# placa_taca_2_0.net
KiCad netlist of a schematic drawn in EAGLE
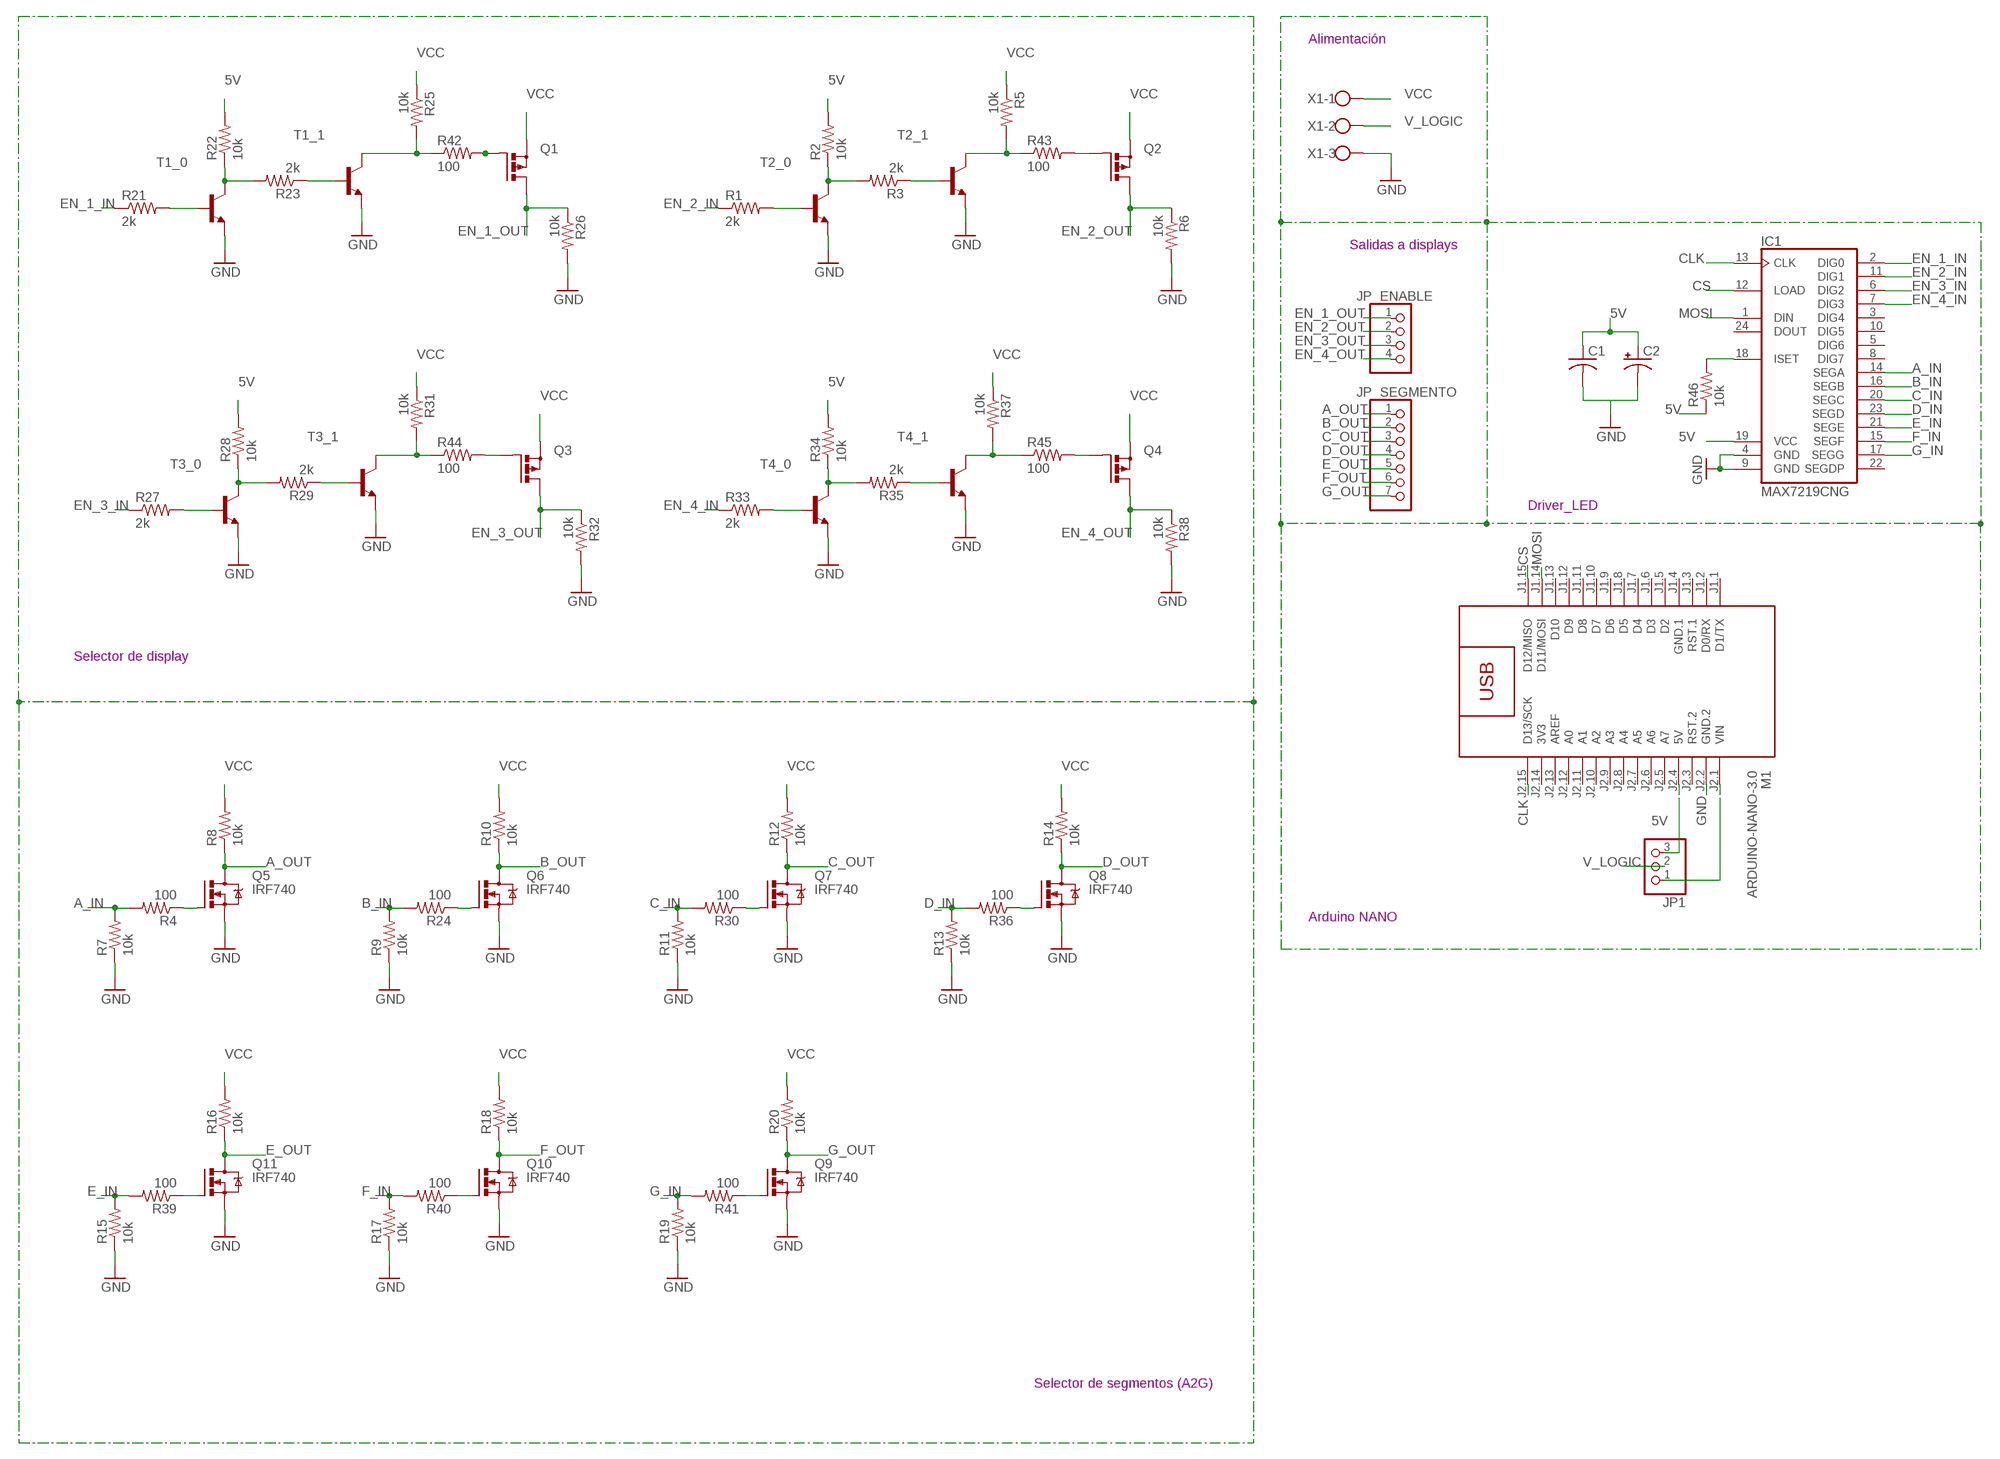
[diagram p0: schematic, sheet 1]

(export (version "E")
  (design (tool "Eeschema 10.0.6"))
  (components
    (comp (ref "C1")
      (value "C-US025-030X050")
      (footprint "eagle-import:C025-030X050")
      (libsource (lib "eagle-import") (part "C-US025-030X050"))
    )
    (comp (ref "C2")
      (value "CPOL-USE2.5-5")
      (footprint "eagle-import:E2,5-5")
      (libsource (lib "eagle-import") (part "CPOL-USE2.5-5"))
    )
    (comp (ref "IC1")
      (value "MAX7219CNG")
      (footprint "eagle-import:DIL24-3")
      (fields (field (name "MF") "MAXIM"))
      (libsource (lib "eagle-import") (part "MAX7219CNG"))
    )
    (comp (ref "JP1")
      (value "PINHD-1X3")
      (footprint "eagle-import:1X03")
      (libsource (lib "eagle-import") (part "PINHD-1X3"))
    )
    (comp (ref "JP_ENABLE")
      (value "PINHD-1X4")
      (footprint "eagle-import:1X04")
      (libsource (lib "eagle-import") (part "PINHD-1X4"))
    )
    (comp (ref "JP_SEGMENTO")
      (value "PINHD-1X7")
      (footprint "eagle-import:1X07")
      (libsource (lib "eagle-import") (part "PINHD-1X7"))
    )
    (comp (ref "M1")
      (value "ARDUINO-NANO-3.0")
      (footprint "eagle-import:ARDUINO-NANO-3.0")
      (libsource (lib "eagle-import") (part "ARDUINO-NANO-3.0"))
    )
    (comp (ref "Q1")
      (value "PMOSFET_PTO220BV")
      (footprint "eagle-import:TO220BV")
      (libsource (lib "eagle-import") (part "PMOSFET_PTO220BV"))
    )
    (comp (ref "Q2")
      (value "PMOSFET_PTO220BV")
      (footprint "eagle-import:TO220BV")
      (libsource (lib "eagle-import") (part "PMOSFET_PTO220BV"))
    )
    (comp (ref "Q3")
      (value "PMOSFET_PTO220BV")
      (footprint "eagle-import:TO220BV")
      (libsource (lib "eagle-import") (part "PMOSFET_PTO220BV"))
    )
    (comp (ref "Q4")
      (value "PMOSFET_PTO220BV")
      (footprint "eagle-import:TO220BV")
      (libsource (lib "eagle-import") (part "PMOSFET_PTO220BV"))
    )
    (comp (ref "Q5")
      (value "IRF740")
      (footprint "eagle-import:TO220BV")
      (libsource (lib "eagle-import") (part "IRF740"))
    )
    (comp (ref "Q6")
      (value "IRF740")
      (footprint "eagle-import:TO220BV")
      (libsource (lib "eagle-import") (part "IRF740"))
    )
    (comp (ref "Q7")
      (value "IRF740")
      (footprint "eagle-import:TO220BV")
      (libsource (lib "eagle-import") (part "IRF740"))
    )
    (comp (ref "Q8")
      (value "IRF740")
      (footprint "eagle-import:TO220BV")
      (libsource (lib "eagle-import") (part "IRF740"))
    )
    (comp (ref "Q9")
      (value "IRF740")
      (footprint "eagle-import:TO220BV")
      (libsource (lib "eagle-import") (part "IRF740"))
    )
    (comp (ref "Q10")
      (value "IRF740")
      (footprint "eagle-import:TO220BV")
      (libsource (lib "eagle-import") (part "IRF740"))
    )
    (comp (ref "Q11")
      (value "IRF740")
      (footprint "eagle-import:TO220BV")
      (libsource (lib "eagle-import") (part "IRF740"))
    )
    (comp (ref "R1")
      (value "2k")
      (footprint "eagle-import:0207_10")
      (libsource (lib "eagle-import") (part "R-US_0207/10"))
    )
    (comp (ref "R2")
      (value "10k")
      (footprint "eagle-import:0207_10")
      (libsource (lib "eagle-import") (part "R-US_0207/10"))
    )
    (comp (ref "R3")
      (value "2k")
      (footprint "eagle-import:0207_10")
      (libsource (lib "eagle-import") (part "R-US_0207/10"))
    )
    (comp (ref "R4")
      (value "100")
      (footprint "eagle-import:0207_10")
      (libsource (lib "eagle-import") (part "R-US_0207/10"))
    )
    (comp (ref "R5")
      (value "10k")
      (footprint "eagle-import:0207_10")
      (libsource (lib "eagle-import") (part "R-US_0207/10"))
    )
    (comp (ref "R6")
      (value "10k")
      (footprint "eagle-import:0207_10")
      (libsource (lib "eagle-import") (part "R-US_0207/10"))
    )
    (comp (ref "R7")
      (value "10k")
      (footprint "eagle-import:0207_10")
      (libsource (lib "eagle-import") (part "R-US_0207/10"))
    )
    (comp (ref "R8")
      (value "10k")
      (footprint "eagle-import:0207_10")
      (libsource (lib "eagle-import") (part "R-US_0207/10"))
    )
    (comp (ref "R9")
      (value "10k")
      (footprint "eagle-import:0207_10")
      (libsource (lib "eagle-import") (part "R-US_0207/10"))
    )
    (comp (ref "R10")
      (value "10k")
      (footprint "eagle-import:0207_10")
      (libsource (lib "eagle-import") (part "R-US_0207/10"))
    )
    (comp (ref "R11")
      (value "10k")
      (footprint "eagle-import:0207_10")
      (libsource (lib "eagle-import") (part "R-US_0207/10"))
    )
    (comp (ref "R12")
      (value "10k")
      (footprint "eagle-import:0207_10")
      (libsource (lib "eagle-import") (part "R-US_0207/10"))
    )
    (comp (ref "R13")
      (value "10k")
      (footprint "eagle-import:0207_10")
      (libsource (lib "eagle-import") (part "R-US_0207/10"))
    )
    (comp (ref "R14")
      (value "10k")
      (footprint "eagle-import:0207_10")
      (libsource (lib "eagle-import") (part "R-US_0207/10"))
    )
    (comp (ref "R15")
      (value "10k")
      (footprint "eagle-import:0207_10")
      (libsource (lib "eagle-import") (part "R-US_0207/10"))
    )
    (comp (ref "R16")
      (value "10k")
      (footprint "eagle-import:0207_10")
      (libsource (lib "eagle-import") (part "R-US_0207/10"))
    )
    (comp (ref "R17")
      (value "10k")
      (footprint "eagle-import:0207_10")
      (libsource (lib "eagle-import") (part "R-US_0207/10"))
    )
    (comp (ref "R18")
      (value "10k")
      (footprint "eagle-import:0207_10")
      (libsource (lib "eagle-import") (part "R-US_0207/10"))
    )
    (comp (ref "R19")
      (value "10k")
      (footprint "eagle-import:0207_10")
      (libsource (lib "eagle-import") (part "R-US_0207/10"))
    )
    (comp (ref "R20")
      (value "10k")
      (footprint "eagle-import:0207_10")
      (libsource (lib "eagle-import") (part "R-US_0207/10"))
    )
    (comp (ref "R21")
      (value "2k")
      (footprint "eagle-import:0207_10")
      (libsource (lib "eagle-import") (part "R-US_0207/10"))
    )
    (comp (ref "R22")
      (value "10k")
      (footprint "eagle-import:0207_10")
      (libsource (lib "eagle-import") (part "R-US_0207/10"))
    )
    (comp (ref "R23")
      (value "2k")
      (footprint "eagle-import:0207_10")
      (libsource (lib "eagle-import") (part "R-US_0207/10"))
    )
    (comp (ref "R24")
      (value "100")
      (footprint "eagle-import:0207_10")
      (libsource (lib "eagle-import") (part "R-US_0207/10"))
    )
    (comp (ref "R25")
      (value "10k")
      (footprint "eagle-import:0207_10")
      (libsource (lib "eagle-import") (part "R-US_0207/10"))
    )
    (comp (ref "R26")
      (value "10k")
      (footprint "eagle-import:0207_10")
      (libsource (lib "eagle-import") (part "R-US_0207/10"))
    )
    (comp (ref "R27")
      (value "2k")
      (footprint "eagle-import:0207_10")
      (libsource (lib "eagle-import") (part "R-US_0207/10"))
    )
    (comp (ref "R28")
      (value "10k")
      (footprint "eagle-import:0207_10")
      (libsource (lib "eagle-import") (part "R-US_0207/10"))
    )
    (comp (ref "R29")
      (value "2k")
      (footprint "eagle-import:0207_10")
      (libsource (lib "eagle-import") (part "R-US_0207/10"))
    )
    (comp (ref "R30")
      (value "100")
      (footprint "eagle-import:0207_10")
      (libsource (lib "eagle-import") (part "R-US_0207/10"))
    )
    (comp (ref "R31")
      (value "10k")
      (footprint "eagle-import:0207_10")
      (libsource (lib "eagle-import") (part "R-US_0207/10"))
    )
    (comp (ref "R32")
      (value "10k")
      (footprint "eagle-import:0207_10")
      (libsource (lib "eagle-import") (part "R-US_0207/10"))
    )
    (comp (ref "R33")
      (value "2k")
      (footprint "eagle-import:0207_10")
      (libsource (lib "eagle-import") (part "R-US_0207/10"))
    )
    (comp (ref "R34")
      (value "10k")
      (footprint "eagle-import:0207_10")
      (libsource (lib "eagle-import") (part "R-US_0207/10"))
    )
    (comp (ref "R35")
      (value "2k")
      (footprint "eagle-import:0207_10")
      (libsource (lib "eagle-import") (part "R-US_0207/10"))
    )
    (comp (ref "R36")
      (value "100")
      (footprint "eagle-import:0207_10")
      (libsource (lib "eagle-import") (part "R-US_0207/10"))
    )
    (comp (ref "R37")
      (value "10k")
      (footprint "eagle-import:0207_10")
      (libsource (lib "eagle-import") (part "R-US_0207/10"))
    )
    (comp (ref "R38")
      (value "10k")
      (footprint "eagle-import:0207_10")
      (libsource (lib "eagle-import") (part "R-US_0207/10"))
    )
    (comp (ref "R39")
      (value "100")
      (footprint "eagle-import:0207_10")
      (libsource (lib "eagle-import") (part "R-US_0207/10"))
    )
    (comp (ref "R40")
      (value "100")
      (footprint "eagle-import:0207_10")
      (libsource (lib "eagle-import") (part "R-US_0207/10"))
    )
    (comp (ref "R41")
      (value "100")
      (footprint "eagle-import:0207_10")
      (libsource (lib "eagle-import") (part "R-US_0207/10"))
    )
    (comp (ref "R42")
      (value "100")
      (footprint "eagle-import:0207_10")
      (libsource (lib "eagle-import") (part "R-US_0207/10"))
    )
    (comp (ref "R43")
      (value "100")
      (footprint "eagle-import:0207_10")
      (libsource (lib "eagle-import") (part "R-US_0207/10"))
    )
    (comp (ref "R44")
      (value "100")
      (footprint "eagle-import:0207_10")
      (libsource (lib "eagle-import") (part "R-US_0207/10"))
    )
    (comp (ref "R45")
      (value "100")
      (footprint "eagle-import:0207_10")
      (libsource (lib "eagle-import") (part "R-US_0207/10"))
    )
    (comp (ref "R46")
      (value "10k")
      (footprint "eagle-import:0207_10")
      (libsource (lib "eagle-import") (part "R-US_0207/10"))
    )
    (comp (ref "T1_0")
      (value "2N2222-NPN-TO92-EBC")
      (footprint "eagle-import:TO92-EBC")
      (libsource (lib "eagle-import") (part "-NPN-TO92-EBC2N2222"))
    )
    (comp (ref "T1_1")
      (value "2N2222-NPN-TO92-EBC")
      (footprint "eagle-import:TO92-EBC")
      (libsource (lib "eagle-import") (part "-NPN-TO92-EBC2N2222"))
    )
    (comp (ref "T2_0")
      (value "2N2222-NPN-TO92-EBC")
      (footprint "eagle-import:TO92-EBC")
      (libsource (lib "eagle-import") (part "-NPN-TO92-EBC2N2222"))
    )
    (comp (ref "T2_1")
      (value "2N2222-NPN-TO92-EBC")
      (footprint "eagle-import:TO92-EBC")
      (libsource (lib "eagle-import") (part "-NPN-TO92-EBC2N2222"))
    )
    (comp (ref "T3_0")
      (value "2N2222-NPN-TO92-EBC")
      (footprint "eagle-import:TO92-EBC")
      (libsource (lib "eagle-import") (part "-NPN-TO92-EBC2N2222"))
    )
    (comp (ref "T3_1")
      (value "2N2222-NPN-TO92-EBC")
      (footprint "eagle-import:TO92-EBC")
      (libsource (lib "eagle-import") (part "-NPN-TO92-EBC2N2222"))
    )
    (comp (ref "T4_0")
      (value "2N2222-NPN-TO92-EBC")
      (footprint "eagle-import:TO92-EBC")
      (libsource (lib "eagle-import") (part "-NPN-TO92-EBC2N2222"))
    )
    (comp (ref "T4_1")
      (value "2N2222-NPN-TO92-EBC")
      (footprint "eagle-import:TO92-EBC")
      (libsource (lib "eagle-import") (part "-NPN-TO92-EBC2N2222"))
    )
    (comp (ref "X1")
      (value "W237-103")
      (footprint "eagle-import:W237-103")
      (fields (field (name "MPN") "237-103"))
      (libsource (lib "eagle-import") (part "W237-103"))
    )
  )
  (nets
    (net (code "1") (name "/3V3") (class "Default")
      (node (ref "M1") (pin "J2.14") (pinfunction "3V3_J2.14") (pintype "power_in"))
    )
    (net (code "2") (name "/5V") (class "Default")
      (node (ref "C1") (pin "1") (pinfunction "1_1") (pintype "passive"))
      (node (ref "C2") (pin "+") (pinfunction "+_+") (pintype "passive"))
      (node (ref "IC1") (pin "19") (pinfunction "VCC_19") (pintype "power_in"))
      (node (ref "JP1") (pin "3") (pinfunction "3_3") (pintype "passive"))
      (node (ref "M1") (pin "J2.4") (pinfunction "5V_J2.4") (pintype "power_in"))
      (node (ref "R2") (pin "2") (pinfunction "2_2") (pintype "passive"))
      (node (ref "R22") (pin "2") (pinfunction "2_2") (pintype "passive"))
      (node (ref "R28") (pin "2") (pinfunction "2_2") (pintype "passive"))
      (node (ref "R34") (pin "2") (pinfunction "2_2") (pintype "passive"))
      (node (ref "R46") (pin "1") (pinfunction "1_1") (pintype "passive"))
    )
    (net (code "3") (name "/A_IN") (class "Default")
      (node (ref "IC1") (pin "14") (pinfunction "SEGA_14") (pintype "output"))
      (node (ref "R4") (pin "2") (pinfunction "2_2") (pintype "passive"))
      (node (ref "R7") (pin "2") (pinfunction "2_2") (pintype "passive"))
    )
    (net (code "4") (name "/A_OUT") (class "Default")
      (node (ref "JP_SEGMENTO") (pin "1") (pinfunction "1_1") (pintype "passive"))
      (node (ref "Q5") (pin "D") (pinfunction "D_D") (pintype "passive"))
      (node (ref "R8") (pin "1") (pinfunction "1_1") (pintype "passive"))
    )
    (net (code "5") (name "/B_IN") (class "Default")
      (node (ref "IC1") (pin "16") (pinfunction "SEGB_16") (pintype "output"))
      (node (ref "R24") (pin "2") (pinfunction "2_2") (pintype "passive"))
      (node (ref "R9") (pin "2") (pinfunction "2_2") (pintype "passive"))
    )
    (net (code "6") (name "/B_OUT") (class "Default")
      (node (ref "JP_SEGMENTO") (pin "2") (pinfunction "2_2") (pintype "passive"))
      (node (ref "Q6") (pin "D") (pinfunction "D_D") (pintype "passive"))
      (node (ref "R10") (pin "1") (pinfunction "1_1") (pintype "passive"))
    )
    (net (code "7") (name "/CLK") (class "Default")
      (node (ref "IC1") (pin "13") (pinfunction "CLK_13") (pintype "input"))
      (node (ref "M1") (pin "J2.15") (pinfunction "D13/SCK_J2.15") (pintype "bidirectional"))
    )
    (net (code "8") (name "/CS") (class "Default")
      (node (ref "IC1") (pin "12") (pinfunction "LOAD_12") (pintype "input"))
      (node (ref "M1") (pin "J1.15") (pinfunction "D12/MISO_J1.15") (pintype "bidirectional"))
    )
    (net (code "9") (name "/C_IN") (class "Default")
      (node (ref "IC1") (pin "20") (pinfunction "SEGC_20") (pintype "output"))
      (node (ref "R11") (pin "2") (pinfunction "2_2") (pintype "passive"))
      (node (ref "R30") (pin "2") (pinfunction "2_2") (pintype "passive"))
    )
    (net (code "10") (name "/C_OUT") (class "Default")
      (node (ref "JP_SEGMENTO") (pin "3") (pinfunction "3_3") (pintype "passive"))
      (node (ref "Q7") (pin "D") (pinfunction "D_D") (pintype "passive"))
      (node (ref "R12") (pin "1") (pinfunction "1_1") (pintype "passive"))
    )
    (net (code "11") (name "/D_IN") (class "Default")
      (node (ref "IC1") (pin "23") (pinfunction "SEGD_23") (pintype "output"))
      (node (ref "R13") (pin "2") (pinfunction "2_2") (pintype "passive"))
      (node (ref "R36") (pin "2") (pinfunction "2_2") (pintype "passive"))
    )
    (net (code "12") (name "/D_OUT") (class "Default")
      (node (ref "JP_SEGMENTO") (pin "4") (pinfunction "4_4") (pintype "passive"))
      (node (ref "Q8") (pin "D") (pinfunction "D_D") (pintype "passive"))
      (node (ref "R14") (pin "1") (pinfunction "1_1") (pintype "passive"))
    )
    (net (code "13") (name "/EN_1_IN") (class "Default")
      (node (ref "IC1") (pin "2") (pinfunction "DIG0_2") (pintype "output"))
      (node (ref "R21") (pin "1") (pinfunction "1_1") (pintype "passive"))
    )
    (net (code "14") (name "/EN_1_OUT") (class "Default")
      (node (ref "JP_ENABLE") (pin "1") (pinfunction "1_1") (pintype "passive"))
      (node (ref "Q1") (pin "D") (pinfunction "D_D") (pintype "passive"))
      (node (ref "R26") (pin "1") (pinfunction "1_1") (pintype "passive"))
    )
    (net (code "15") (name "/EN_2_IN") (class "Default")
      (node (ref "IC1") (pin "11") (pinfunction "DIG1_11") (pintype "output"))
      (node (ref "R1") (pin "1") (pinfunction "1_1") (pintype "passive"))
    )
    (net (code "16") (name "/EN_2_OUT") (class "Default")
      (node (ref "JP_ENABLE") (pin "2") (pinfunction "2_2") (pintype "passive"))
      (node (ref "Q2") (pin "D") (pinfunction "D_D") (pintype "passive"))
      (node (ref "R6") (pin "1") (pinfunction "1_1") (pintype "passive"))
    )
    (net (code "17") (name "/EN_3_IN") (class "Default")
      (node (ref "IC1") (pin "6") (pinfunction "DIG2_6") (pintype "output"))
      (node (ref "R27") (pin "1") (pinfunction "1_1") (pintype "passive"))
    )
    (net (code "18") (name "/EN_3_OUT") (class "Default")
      (node (ref "JP_ENABLE") (pin "3") (pinfunction "3_3") (pintype "passive"))
      (node (ref "Q3") (pin "D") (pinfunction "D_D") (pintype "passive"))
      (node (ref "R32") (pin "1") (pinfunction "1_1") (pintype "passive"))
    )
    (net (code "19") (name "/EN_4_IN") (class "Default")
      (node (ref "IC1") (pin "7") (pinfunction "DIG3_7") (pintype "output"))
      (node (ref "R33") (pin "1") (pinfunction "1_1") (pintype "passive"))
    )
    (net (code "20") (name "/EN_4_OUT") (class "Default")
      (node (ref "JP_ENABLE") (pin "4") (pinfunction "4_4") (pintype "passive"))
      (node (ref "Q4") (pin "D") (pinfunction "D_D") (pintype "passive"))
      (node (ref "R38") (pin "1") (pinfunction "1_1") (pintype "passive"))
    )
    (net (code "21") (name "/E_IN") (class "Default")
      (node (ref "IC1") (pin "21") (pinfunction "SEGE_21") (pintype "output"))
      (node (ref "R15") (pin "2") (pinfunction "2_2") (pintype "passive"))
      (node (ref "R39") (pin "2") (pinfunction "2_2") (pintype "passive"))
    )
    (net (code "22") (name "/E_OUT") (class "Default")
      (node (ref "JP_SEGMENTO") (pin "5") (pinfunction "5_5") (pintype "passive"))
      (node (ref "Q11") (pin "D") (pinfunction "D_D") (pintype "passive"))
      (node (ref "R16") (pin "1") (pinfunction "1_1") (pintype "passive"))
    )
    (net (code "23") (name "/F_IN") (class "Default")
      (node (ref "IC1") (pin "15") (pinfunction "SEGF_15") (pintype "output"))
      (node (ref "R17") (pin "2") (pinfunction "2_2") (pintype "passive"))
      (node (ref "R40") (pin "2") (pinfunction "2_2") (pintype "passive"))
    )
    (net (code "24") (name "/F_OUT") (class "Default")
      (node (ref "JP_SEGMENTO") (pin "6") (pinfunction "6_6") (pintype "passive"))
      (node (ref "Q10") (pin "D") (pinfunction "D_D") (pintype "passive"))
      (node (ref "R18") (pin "1") (pinfunction "1_1") (pintype "passive"))
    )
    (net (code "25") (name "/GND.1") (class "Default")
      (node (ref "M1") (pin "J1.4") (pinfunction "GND.1_J1.4") (pintype "power_in"))
    )
    (net (code "26") (name "/G_IN") (class "Default")
      (node (ref "IC1") (pin "17") (pinfunction "SEGG_17") (pintype "output"))
      (node (ref "R19") (pin "2") (pinfunction "2_2") (pintype "passive"))
      (node (ref "R41") (pin "2") (pinfunction "2_2") (pintype "passive"))
    )
    (net (code "27") (name "/G_OUT") (class "Default")
      (node (ref "JP_SEGMENTO") (pin "7") (pinfunction "7_7") (pintype "passive"))
      (node (ref "Q9") (pin "D") (pinfunction "D_D") (pintype "passive"))
      (node (ref "R20") (pin "1") (pinfunction "1_1") (pintype "passive"))
    )
    (net (code "28") (name "/MOSI") (class "Default")
      (node (ref "IC1") (pin "1") (pinfunction "DIN_1") (pintype "input"))
      (node (ref "M1") (pin "J1.14") (pinfunction "D11/MOSI_J1.14") (pintype "bidirectional"))
    )
    (net (code "29") (name "/VCC") (class "Default")
      (node (ref "Q1") (pin "S") (pinfunction "S_S") (pintype "passive"))
      (node (ref "Q2") (pin "S") (pinfunction "S_S") (pintype "passive"))
      (node (ref "Q3") (pin "S") (pinfunction "S_S") (pintype "passive"))
      (node (ref "Q4") (pin "S") (pinfunction "S_S") (pintype "passive"))
      (node (ref "R10") (pin "2") (pinfunction "2_2") (pintype "passive"))
      (node (ref "R12") (pin "2") (pinfunction "2_2") (pintype "passive"))
      (node (ref "R14") (pin "2") (pinfunction "2_2") (pintype "passive"))
      (node (ref "R16") (pin "2") (pinfunction "2_2") (pintype "passive"))
      (node (ref "R18") (pin "2") (pinfunction "2_2") (pintype "passive"))
      (node (ref "R20") (pin "2") (pinfunction "2_2") (pintype "passive"))
      (node (ref "R25") (pin "1") (pinfunction "1_1") (pintype "passive"))
      (node (ref "R31") (pin "1") (pinfunction "1_1") (pintype "passive"))
      (node (ref "R37") (pin "1") (pinfunction "1_1") (pintype "passive"))
      (node (ref "R5") (pin "1") (pinfunction "1_1") (pintype "passive"))
      (node (ref "R8") (pin "2") (pinfunction "2_2") (pintype "passive"))
      (node (ref "X1") (pin "1") (pinfunction "KL_1") (pintype "passive"))
    )
    (net (code "30") (name "/V_LOGIC") (class "Default")
      (node (ref "JP1") (pin "2") (pinfunction "2_2") (pintype "passive"))
      (node (ref "X1") (pin "2") (pinfunction "KL_2") (pintype "passive"))
    )
    (net (code "31") (name "GND") (class "Default")
      (node (ref "IC1") (pin "4") (pinfunction "GND_4") (pintype "power_in"))
      (node (ref "IC1") (pin "9") (pinfunction "GND_9") (pintype "power_in"))
      (node (ref "M1") (pin "J2.2") (pinfunction "GND.2_J2.2") (pintype "power_in"))
      (node (ref "Q10") (pin "S") (pinfunction "S_S") (pintype "passive"))
      (node (ref "Q11") (pin "S") (pinfunction "S_S") (pintype "passive"))
      (node (ref "Q5") (pin "S") (pinfunction "S_S") (pintype "passive"))
      (node (ref "Q6") (pin "S") (pinfunction "S_S") (pintype "passive"))
      (node (ref "Q7") (pin "S") (pinfunction "S_S") (pintype "passive"))
      (node (ref "Q8") (pin "S") (pinfunction "S_S") (pintype "passive"))
      (node (ref "Q9") (pin "S") (pinfunction "S_S") (pintype "passive"))
      (node (ref "R11") (pin "1") (pinfunction "1_1") (pintype "passive"))
      (node (ref "R13") (pin "1") (pinfunction "1_1") (pintype "passive"))
      (node (ref "R15") (pin "1") (pinfunction "1_1") (pintype "passive"))
      (node (ref "R17") (pin "1") (pinfunction "1_1") (pintype "passive"))
      (node (ref "R19") (pin "1") (pinfunction "1_1") (pintype "passive"))
      (node (ref "R26") (pin "2") (pinfunction "2_2") (pintype "passive"))
      (node (ref "R32") (pin "2") (pinfunction "2_2") (pintype "passive"))
      (node (ref "R38") (pin "2") (pinfunction "2_2") (pintype "passive"))
      (node (ref "R6") (pin "2") (pinfunction "2_2") (pintype "passive"))
      (node (ref "R7") (pin "1") (pinfunction "1_1") (pintype "passive"))
      (node (ref "R9") (pin "1") (pinfunction "1_1") (pintype "passive"))
      (node (ref "T1_0") (pin "E") (pinfunction "E_E") (pintype "passive"))
      (node (ref "T1_1") (pin "E") (pinfunction "E_E") (pintype "passive"))
      (node (ref "T2_0") (pin "E") (pinfunction "E_E") (pintype "passive"))
      (node (ref "T2_1") (pin "E") (pinfunction "E_E") (pintype "passive"))
      (node (ref "T3_0") (pin "E") (pinfunction "E_E") (pintype "passive"))
      (node (ref "T3_1") (pin "E") (pinfunction "E_E") (pintype "passive"))
      (node (ref "T4_0") (pin "E") (pinfunction "E_E") (pintype "passive"))
      (node (ref "T4_1") (pin "E") (pinfunction "E_E") (pintype "passive"))
      (node (ref "X1") (pin "3") (pinfunction "KL_3") (pintype "passive"))
    )
    (net (code "32") (name "Net-(C1-Pad2)") (class "Default")
      (node (ref "C1") (pin "2") (pinfunction "2_2") (pintype "passive"))
      (node (ref "C2") (pin "-") (pinfunction "-_-") (pintype "passive"))
    )
    (net (code "33") (name "Net-(IC1-ISET)") (class "Default")
      (node (ref "IC1") (pin "18") (pinfunction "ISET_18") (pintype "input"))
      (node (ref "R46") (pin "2") (pinfunction "2_2") (pintype "passive"))
    )
    (net (code "34") (name "Net-(M1-VIN)") (class "Default")
      (node (ref "JP1") (pin "1") (pinfunction "1_1") (pintype "passive"))
      (node (ref "M1") (pin "J2.1") (pinfunction "VIN_J2.1") (pintype "power_in"))
    )
    (net (code "35") (name "Net-(Q1-PadG)") (class "Default")
      (node (ref "Q1") (pin "G") (pinfunction "G_G") (pintype "passive"))
      (node (ref "R42") (pin "2") (pinfunction "2_2") (pintype "passive"))
    )
    (net (code "36") (name "Net-(Q2-PadG)") (class "Default")
      (node (ref "Q2") (pin "G") (pinfunction "G_G") (pintype "passive"))
      (node (ref "R43") (pin "2") (pinfunction "2_2") (pintype "passive"))
    )
    (net (code "37") (name "Net-(Q3-PadG)") (class "Default")
      (node (ref "Q3") (pin "G") (pinfunction "G_G") (pintype "passive"))
      (node (ref "R44") (pin "2") (pinfunction "2_2") (pintype "passive"))
    )
    (net (code "38") (name "Net-(Q4-PadG)") (class "Default")
      (node (ref "Q4") (pin "G") (pinfunction "G_G") (pintype "passive"))
      (node (ref "R45") (pin "2") (pinfunction "2_2") (pintype "passive"))
    )
    (net (code "39") (name "Net-(Q5-PadG)") (class "Default")
      (node (ref "Q5") (pin "G") (pinfunction "G_G") (pintype "passive"))
      (node (ref "R4") (pin "1") (pinfunction "1_1") (pintype "passive"))
    )
    (net (code "40") (name "Net-(Q6-PadG)") (class "Default")
      (node (ref "Q6") (pin "G") (pinfunction "G_G") (pintype "passive"))
      (node (ref "R24") (pin "1") (pinfunction "1_1") (pintype "passive"))
    )
    (net (code "41") (name "Net-(Q7-PadG)") (class "Default")
      (node (ref "Q7") (pin "G") (pinfunction "G_G") (pintype "passive"))
      (node (ref "R30") (pin "1") (pinfunction "1_1") (pintype "passive"))
    )
    (net (code "42") (name "Net-(Q8-PadG)") (class "Default")
      (node (ref "Q8") (pin "G") (pinfunction "G_G") (pintype "passive"))
      (node (ref "R36") (pin "1") (pinfunction "1_1") (pintype "passive"))
    )
    (net (code "43") (name "Net-(Q9-PadG)") (class "Default")
      (node (ref "Q9") (pin "G") (pinfunction "G_G") (pintype "passive"))
      (node (ref "R41") (pin "1") (pinfunction "1_1") (pintype "passive"))
    )
    (net (code "44") (name "Net-(Q10-PadG)") (class "Default")
      (node (ref "Q10") (pin "G") (pinfunction "G_G") (pintype "passive"))
      (node (ref "R40") (pin "1") (pinfunction "1_1") (pintype "passive"))
    )
    (net (code "45") (name "Net-(Q11-PadG)") (class "Default")
      (node (ref "Q11") (pin "G") (pinfunction "G_G") (pintype "passive"))
      (node (ref "R39") (pin "1") (pinfunction "1_1") (pintype "passive"))
    )
    (net (code "46") (name "Net-(R1-Pad2)") (class "Default")
      (node (ref "R1") (pin "2") (pinfunction "2_2") (pintype "passive"))
      (node (ref "T2_0") (pin "B") (pinfunction "B_B") (pintype "passive"))
    )
    (net (code "47") (name "Net-(R2-Pad1)") (class "Default")
      (node (ref "R2") (pin "1") (pinfunction "1_1") (pintype "passive"))
      (node (ref "R3") (pin "2") (pinfunction "2_2") (pintype "passive"))
      (node (ref "T2_0") (pin "C") (pinfunction "C_C") (pintype "passive"))
    )
    (net (code "48") (name "Net-(R3-Pad1)") (class "Default")
      (node (ref "R3") (pin "1") (pinfunction "1_1") (pintype "passive"))
      (node (ref "T2_1") (pin "B") (pinfunction "B_B") (pintype "passive"))
    )
    (net (code "49") (name "Net-(R21-Pad2)") (class "Default")
      (node (ref "R21") (pin "2") (pinfunction "2_2") (pintype "passive"))
      (node (ref "T1_0") (pin "B") (pinfunction "B_B") (pintype "passive"))
    )
    (net (code "50") (name "Net-(R22-Pad1)") (class "Default")
      (node (ref "R22") (pin "1") (pinfunction "1_1") (pintype "passive"))
      (node (ref "R23") (pin "2") (pinfunction "2_2") (pintype "passive"))
      (node (ref "T1_0") (pin "C") (pinfunction "C_C") (pintype "passive"))
    )
    (net (code "51") (name "Net-(R23-Pad1)") (class "Default")
      (node (ref "R23") (pin "1") (pinfunction "1_1") (pintype "passive"))
      (node (ref "T1_1") (pin "B") (pinfunction "B_B") (pintype "passive"))
    )
    (net (code "52") (name "Net-(R25-Pad2)") (class "Default")
      (node (ref "R25") (pin "2") (pinfunction "2_2") (pintype "passive"))
      (node (ref "R42") (pin "1") (pinfunction "1_1") (pintype "passive"))
      (node (ref "T1_1") (pin "C") (pinfunction "C_C") (pintype "passive"))
    )
    (net (code "53") (name "Net-(R27-Pad2)") (class "Default")
      (node (ref "R27") (pin "2") (pinfunction "2_2") (pintype "passive"))
      (node (ref "T3_0") (pin "B") (pinfunction "B_B") (pintype "passive"))
    )
    (net (code "54") (name "Net-(R28-Pad1)") (class "Default")
      (node (ref "R28") (pin "1") (pinfunction "1_1") (pintype "passive"))
      (node (ref "R29") (pin "2") (pinfunction "2_2") (pintype "passive"))
      (node (ref "T3_0") (pin "C") (pinfunction "C_C") (pintype "passive"))
    )
    (net (code "55") (name "Net-(R29-Pad1)") (class "Default")
      (node (ref "R29") (pin "1") (pinfunction "1_1") (pintype "passive"))
      (node (ref "T3_1") (pin "B") (pinfunction "B_B") (pintype "passive"))
    )
    (net (code "56") (name "Net-(R31-Pad2)") (class "Default")
      (node (ref "R31") (pin "2") (pinfunction "2_2") (pintype "passive"))
      (node (ref "R44") (pin "1") (pinfunction "1_1") (pintype "passive"))
      (node (ref "T3_1") (pin "C") (pinfunction "C_C") (pintype "passive"))
    )
    (net (code "57") (name "Net-(R33-Pad2)") (class "Default")
      (node (ref "R33") (pin "2") (pinfunction "2_2") (pintype "passive"))
      (node (ref "T4_0") (pin "B") (pinfunction "B_B") (pintype "passive"))
    )
    (net (code "58") (name "Net-(R34-Pad1)") (class "Default")
      (node (ref "R34") (pin "1") (pinfunction "1_1") (pintype "passive"))
      (node (ref "R35") (pin "2") (pinfunction "2_2") (pintype "passive"))
      (node (ref "T4_0") (pin "C") (pinfunction "C_C") (pintype "passive"))
    )
    (net (code "59") (name "Net-(R35-Pad1)") (class "Default")
      (node (ref "R35") (pin "1") (pinfunction "1_1") (pintype "passive"))
      (node (ref "T4_1") (pin "B") (pinfunction "B_B") (pintype "passive"))
    )
    (net (code "60") (name "Net-(R37-Pad2)") (class "Default")
      (node (ref "R37") (pin "2") (pinfunction "2_2") (pintype "passive"))
      (node (ref "R45") (pin "1") (pinfunction "1_1") (pintype "passive"))
      (node (ref "T4_1") (pin "C") (pinfunction "C_C") (pintype "passive"))
    )
    (net (code "61") (name "Net-(R43-Pad1)") (class "Default")
      (node (ref "R43") (pin "1") (pinfunction "1_1") (pintype "passive"))
      (node (ref "R5") (pin "2") (pinfunction "2_2") (pintype "passive"))
      (node (ref "T2_1") (pin "C") (pinfunction "C_C") (pintype "passive"))
    )
    (net (code "62") (name "unconnected-(IC1-DIG4-Pad3)") (class "Default")
      (node (ref "IC1") (pin "3") (pinfunction "DIG4_3") (pintype "output"))
    )
    (net (code "63") (name "unconnected-(IC1-DIG5-Pad10)") (class "Default")
      (node (ref "IC1") (pin "10") (pinfunction "DIG5_10") (pintype "output"))
    )
    (net (code "64") (name "unconnected-(IC1-DIG6-Pad5)") (class "Default")
      (node (ref "IC1") (pin "5") (pinfunction "DIG6_5") (pintype "output"))
    )
    (net (code "65") (name "unconnected-(IC1-DIG7-Pad8)") (class "Default")
      (node (ref "IC1") (pin "8") (pinfunction "DIG7_8") (pintype "output"))
    )
    (net (code "66") (name "unconnected-(IC1-DOUT-Pad24)") (class "Default")
      (node (ref "IC1") (pin "24") (pinfunction "DOUT_24") (pintype "output"))
    )
    (net (code "67") (name "unconnected-(IC1-SEGDP-Pad22)") (class "Default")
      (node (ref "IC1") (pin "22") (pinfunction "SEGDP_22") (pintype "output"))
    )
    (net (code "68") (name "unconnected-(M1-A0-PadJ2.12)") (class "Default")
      (node (ref "M1") (pin "J2.12") (pinfunction "A0_J2.12") (pintype "bidirectional"))
    )
    (net (code "69") (name "unconnected-(M1-A1-PadJ2.11)") (class "Default")
      (node (ref "M1") (pin "J2.11") (pinfunction "A1_J2.11") (pintype "bidirectional"))
    )
    (net (code "70") (name "unconnected-(M1-A2-PadJ2.10)") (class "Default")
      (node (ref "M1") (pin "J2.10") (pinfunction "A2_J2.10") (pintype "bidirectional"))
    )
    (net (code "71") (name "unconnected-(M1-A3-PadJ2.9)") (class "Default")
      (node (ref "M1") (pin "J2.9") (pinfunction "A3_J2.9") (pintype "bidirectional"))
    )
    (net (code "72") (name "unconnected-(M1-A4-PadJ2.8)") (class "Default")
      (node (ref "M1") (pin "J2.8") (pinfunction "A4_J2.8") (pintype "bidirectional"))
    )
    (net (code "73") (name "unconnected-(M1-A5-PadJ2.7)") (class "Default")
      (node (ref "M1") (pin "J2.7") (pinfunction "A5_J2.7") (pintype "bidirectional"))
    )
    (net (code "74") (name "unconnected-(M1-A6-PadJ2.6)") (class "Default")
      (node (ref "M1") (pin "J2.6") (pinfunction "A6_J2.6") (pintype "bidirectional"))
    )
    (net (code "75") (name "unconnected-(M1-A7-PadJ2.5)") (class "Default")
      (node (ref "M1") (pin "J2.5") (pinfunction "A7_J2.5") (pintype "bidirectional"))
    )
    (net (code "76") (name "unconnected-(M1-AREF-PadJ2.13)") (class "Default")
      (node (ref "M1") (pin "J2.13") (pinfunction "AREF_J2.13") (pintype "bidirectional"))
    )
    (net (code "77") (name "unconnected-(M1-D0{slash}RX-PadJ1.2)") (class "Default")
      (node (ref "M1") (pin "J1.2") (pinfunction "D0/RX_J1.2") (pintype "bidirectional"))
    )
    (net (code "78") (name "unconnected-(M1-D1{slash}TX-PadJ1.1)") (class "Default")
      (node (ref "M1") (pin "J1.1") (pinfunction "D1/TX_J1.1") (pintype "bidirectional"))
    )
    (net (code "79") (name "unconnected-(M1-D2-PadJ1.5)") (class "Default")
      (node (ref "M1") (pin "J1.5") (pinfunction "D2_J1.5") (pintype "bidirectional"))
    )
    (net (code "80") (name "unconnected-(M1-D3-PadJ1.6)") (class "Default")
      (node (ref "M1") (pin "J1.6") (pinfunction "D3_J1.6") (pintype "bidirectional"))
    )
    (net (code "81") (name "unconnected-(M1-D4-PadJ1.7)") (class "Default")
      (node (ref "M1") (pin "J1.7") (pinfunction "D4_J1.7") (pintype "bidirectional"))
    )
    (net (code "82") (name "unconnected-(M1-D5-PadJ1.8)") (class "Default")
      (node (ref "M1") (pin "J1.8") (pinfunction "D5_J1.8") (pintype "bidirectional"))
    )
    (net (code "83") (name "unconnected-(M1-D6-PadJ1.9)") (class "Default")
      (node (ref "M1") (pin "J1.9") (pinfunction "D6_J1.9") (pintype "bidirectional"))
    )
    (net (code "84") (name "unconnected-(M1-D7-PadJ1.10)") (class "Default")
      (node (ref "M1") (pin "J1.10") (pinfunction "D7_J1.10") (pintype "bidirectional"))
    )
    (net (code "85") (name "unconnected-(M1-D8-PadJ1.11)") (class "Default")
      (node (ref "M1") (pin "J1.11") (pinfunction "D8_J1.11") (pintype "bidirectional"))
    )
    (net (code "86") (name "unconnected-(M1-D9-PadJ1.12)") (class "Default")
      (node (ref "M1") (pin "J1.12") (pinfunction "D9_J1.12") (pintype "bidirectional"))
    )
    (net (code "87") (name "unconnected-(M1-D10-PadJ1.13)") (class "Default")
      (node (ref "M1") (pin "J1.13") (pinfunction "D10_J1.13") (pintype "bidirectional"))
    )
    (net (code "88") (name "unconnected-(M1-RST.1-PadJ1.3)") (class "Default")
      (node (ref "M1") (pin "J1.3") (pinfunction "RST.1_J1.3") (pintype "bidirectional"))
    )
    (net (code "89") (name "unconnected-(M1-RST.2-PadJ2.3)") (class "Default")
      (node (ref "M1") (pin "J2.3") (pinfunction "RST.2_J2.3") (pintype "bidirectional"))
    )
  )
)
